# FPGA.net
KiCad netlist of a schematic drawn in Altium Designer
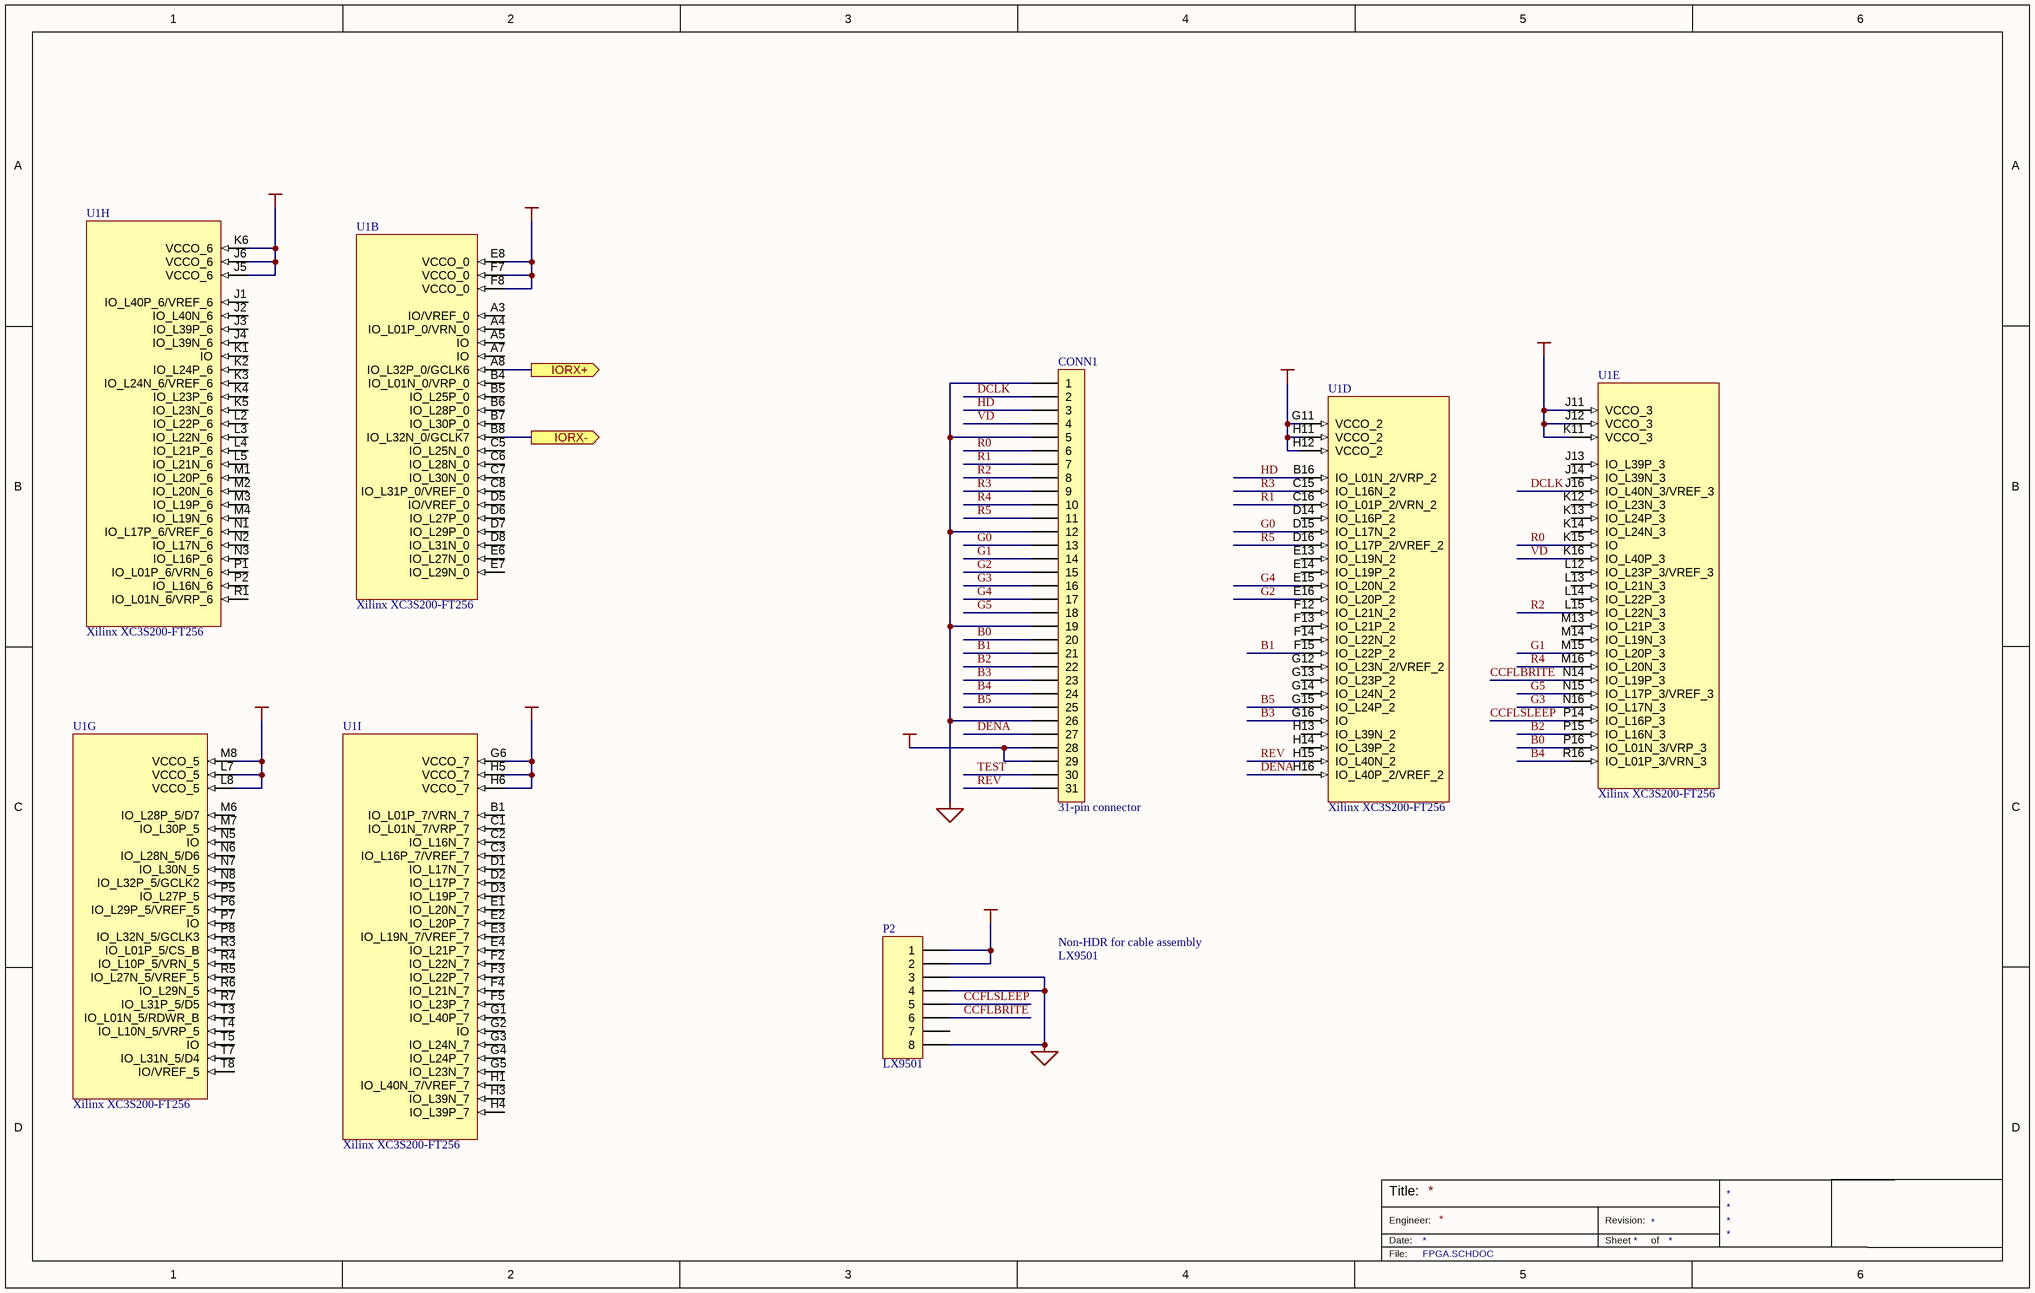
[diagram p0: FPGA.SCHDOC]

(export (version "E")
  (design (tool "Eeschema 10.0.6"))
  (components
    (comp (ref "CONN1")
      (value "31-pin connector")
      (footprint "DF9A-31S-1V")
      (libsource (lib "*") (part "CON31"))
    )
    (comp (ref "P2")
      (value "LX9501")
      (footprint "HDR1X8")
      (description "Header, 8-Pin")
      (fields (field (name "PUBLISHER") "Altium Limited"))
      (libsource (lib "Miscellaneous Connectors") (part "Header 8"))
    )
    (comp (ref "U1")
      (value "Xilinx XC3S200-FT256")
      (footprint "Xilinx FT256 BGA")
      (description "Xilinx Spartan-3 FPGA")
      (libsource (lib "parts") (part "XC3S200-FT256"))
    )
  )
  (nets
    (net (code "1") (name "+2.5VCC") (class "Default")
      (node (ref "U1") (pin "E8") (pinfunction "VCCO_0_E8") (pintype "input"))
      (node (ref "U1") (pin "F7") (pinfunction "VCCO_0_F7") (pintype "input"))
      (node (ref "U1") (pin "F8") (pinfunction "VCCO_0_F8") (pintype "input"))
    )
    (net (code "2") (name "+12VCC") (class "Default")
      (node (ref "P2") (pin "1") (pinfunction "1_1") (pintype "passive"))
      (node (ref "P2") (pin "2") (pinfunction "2_2") (pintype "passive"))
    )
    (net (code "3") (name "/B0") (class "Default")
      (node (ref "CONN1") (pin "20") (pinfunction "20_20") (pintype "passive"))
      (node (ref "U1") (pin "P16") (pinfunction "IO_L01N_3/VRP_3_P16") (pintype "input"))
    )
    (net (code "4") (name "/B1") (class "Default")
      (node (ref "CONN1") (pin "21") (pinfunction "21_21") (pintype "passive"))
      (node (ref "U1") (pin "F15") (pinfunction "IO_L22P_2_F15") (pintype "input"))
    )
    (net (code "5") (name "/B2") (class "Default")
      (node (ref "CONN1") (pin "22") (pinfunction "22_22") (pintype "passive"))
      (node (ref "U1") (pin "P15") (pinfunction "IO_L16N_3_P15") (pintype "input"))
    )
    (net (code "6") (name "/B3") (class "Default")
      (node (ref "CONN1") (pin "23") (pinfunction "23_23") (pintype "passive"))
      (node (ref "U1") (pin "G16") (pinfunction "IO_G16") (pintype "input"))
    )
    (net (code "7") (name "/B4") (class "Default")
      (node (ref "CONN1") (pin "24") (pinfunction "24_24") (pintype "passive"))
      (node (ref "U1") (pin "R16") (pinfunction "IO_L01P_3/VRN_3_R16") (pintype "input"))
    )
    (net (code "8") (name "/B5") (class "Default")
      (node (ref "CONN1") (pin "25") (pinfunction "25_25") (pintype "passive"))
      (node (ref "U1") (pin "G15") (pinfunction "IO_L24P_2_G15") (pintype "input"))
    )
    (net (code "9") (name "/CCFLBRITE") (class "Default")
      (node (ref "P2") (pin "6") (pinfunction "6_6") (pintype "passive"))
      (node (ref "U1") (pin "N14") (pinfunction "IO_L19P_3_N14") (pintype "input"))
    )
    (net (code "10") (name "/CCFLSLEEP") (class "Default")
      (node (ref "P2") (pin "5") (pinfunction "5_5") (pintype "passive"))
      (node (ref "U1") (pin "P14") (pinfunction "IO_L16P_3_P14") (pintype "input"))
    )
    (net (code "11") (name "/DCLK") (class "Default")
      (node (ref "CONN1") (pin "2") (pinfunction "2_2") (pintype "passive"))
      (node (ref "U1") (pin "J16") (pinfunction "IO_L40N_3/VREF_3_J16") (pintype "input"))
    )
    (net (code "12") (name "/DENA") (class "Default")
      (node (ref "CONN1") (pin "27") (pinfunction "27_27") (pintype "passive"))
      (node (ref "U1") (pin "H16") (pinfunction "IO_L40P_2/VREF_2_H16") (pintype "input"))
    )
    (net (code "13") (name "/G0") (class "Default")
      (node (ref "CONN1") (pin "13") (pinfunction "13_13") (pintype "passive"))
      (node (ref "U1") (pin "D15") (pinfunction "IO_L17N_2_D15") (pintype "input"))
    )
    (net (code "14") (name "/G1") (class "Default")
      (node (ref "CONN1") (pin "14") (pinfunction "14_14") (pintype "passive"))
      (node (ref "U1") (pin "M15") (pinfunction "IO_L20P_3_M15") (pintype "input"))
    )
    (net (code "15") (name "/G2") (class "Default")
      (node (ref "CONN1") (pin "15") (pinfunction "15_15") (pintype "passive"))
      (node (ref "U1") (pin "E16") (pinfunction "IO_L20P_2_E16") (pintype "input"))
    )
    (net (code "16") (name "/G3") (class "Default")
      (node (ref "CONN1") (pin "16") (pinfunction "16_16") (pintype "passive"))
      (node (ref "U1") (pin "N16") (pinfunction "IO_L17N_3_N16") (pintype "input"))
    )
    (net (code "17") (name "/G4") (class "Default")
      (node (ref "CONN1") (pin "17") (pinfunction "17_17") (pintype "passive"))
      (node (ref "U1") (pin "E15") (pinfunction "IO_L20N_2_E15") (pintype "input"))
    )
    (net (code "18") (name "/G5") (class "Default")
      (node (ref "CONN1") (pin "18") (pinfunction "18_18") (pintype "passive"))
      (node (ref "U1") (pin "N15") (pinfunction "IO_L17P_3/VREF_3_N15") (pintype "input"))
    )
    (net (code "19") (name "/HD") (class "Default")
      (node (ref "CONN1") (pin "3") (pinfunction "3_3") (pintype "passive"))
      (node (ref "U1") (pin "B16") (pinfunction "IO_L01N_2/VRP_2_B16") (pintype "input"))
    )
    (net (code "20") (name "/IORX+") (class "Default")
      (node (ref "U1") (pin "A8") (pinfunction "IO_L32P_0/GCLK6_A8") (pintype "input"))
    )
    (net (code "21") (name "/IORX-") (class "Default")
      (node (ref "U1") (pin "B8") (pinfunction "IO_L32N_0/GCLK7_B8") (pintype "input"))
    )
    (net (code "22") (name "/R0") (class "Default")
      (node (ref "CONN1") (pin "6") (pinfunction "6_6") (pintype "passive"))
      (node (ref "U1") (pin "K15") (pinfunction "IO_K15") (pintype "input"))
    )
    (net (code "23") (name "/R1") (class "Default")
      (node (ref "CONN1") (pin "7") (pinfunction "7_7") (pintype "passive"))
      (node (ref "U1") (pin "C16") (pinfunction "IO_L01P_2/VRN_2_C16") (pintype "input"))
    )
    (net (code "24") (name "/R2") (class "Default")
      (node (ref "CONN1") (pin "8") (pinfunction "8_8") (pintype "passive"))
      (node (ref "U1") (pin "L15") (pinfunction "IO_L22N_3_L15") (pintype "input"))
    )
    (net (code "25") (name "/R3") (class "Default")
      (node (ref "CONN1") (pin "9") (pinfunction "9_9") (pintype "passive"))
      (node (ref "U1") (pin "C15") (pinfunction "IO_L16N_2_C15") (pintype "input"))
    )
    (net (code "26") (name "/R4") (class "Default")
      (node (ref "CONN1") (pin "10") (pinfunction "10_10") (pintype "passive"))
      (node (ref "U1") (pin "M16") (pinfunction "IO_L20N_3_M16") (pintype "input"))
    )
    (net (code "27") (name "/R5") (class "Default")
      (node (ref "CONN1") (pin "11") (pinfunction "11_11") (pintype "passive"))
      (node (ref "U1") (pin "D16") (pinfunction "IO_L17P_2/VREF_2_D16") (pintype "input"))
    )
    (net (code "28") (name "/REV") (class "Default")
      (node (ref "CONN1") (pin "31") (pinfunction "31_31") (pintype "passive"))
      (node (ref "U1") (pin "H15") (pinfunction "IO_L40N_2_H15") (pintype "input"))
    )
    (net (code "29") (name "/TEST") (class "Default")
      (node (ref "CONN1") (pin "30") (pinfunction "30_30") (pintype "passive"))
    )
    (net (code "30") (name "/VD") (class "Default")
      (node (ref "CONN1") (pin "4") (pinfunction "4_4") (pintype "passive"))
      (node (ref "U1") (pin "K16") (pinfunction "IO_L40P_3_K16") (pintype "input"))
    )
    (net (code "31") (name "GND") (class "Default")
      (node (ref "CONN1") (pin "1") (pinfunction "1_1") (pintype "passive"))
      (node (ref "CONN1") (pin "12") (pinfunction "12_12") (pintype "passive"))
      (node (ref "CONN1") (pin "19") (pinfunction "19_19") (pintype "passive"))
      (node (ref "CONN1") (pin "26") (pinfunction "26_26") (pintype "passive"))
      (node (ref "CONN1") (pin "5") (pinfunction "5_5") (pintype "passive"))
      (node (ref "P2") (pin "3") (pinfunction "3_3") (pintype "passive"))
      (node (ref "P2") (pin "4") (pinfunction "4_4") (pintype "passive"))
      (node (ref "P2") (pin "8") (pinfunction "8_8") (pintype "passive"))
    )
    (net (code "32") (name "VCC") (class "Default")
      (node (ref "CONN1") (pin "28") (pinfunction "28_28") (pintype "passive"))
      (node (ref "CONN1") (pin "29") (pinfunction "29_29") (pintype "passive"))
      (node (ref "U1") (pin "G11") (pinfunction "VCCO_2_G11") (pintype "input"))
      (node (ref "U1") (pin "G6") (pinfunction "VCCO_7_G6") (pintype "input"))
      (node (ref "U1") (pin "H11") (pinfunction "VCCO_2_H11") (pintype "input"))
      (node (ref "U1") (pin "H12") (pinfunction "VCCO_2_H12") (pintype "input"))
      (node (ref "U1") (pin "H5") (pinfunction "VCCO_7_H5") (pintype "input"))
      (node (ref "U1") (pin "H6") (pinfunction "VCCO_7_H6") (pintype "input"))
      (node (ref "U1") (pin "J11") (pinfunction "VCCO_3_J11") (pintype "input"))
      (node (ref "U1") (pin "J12") (pinfunction "VCCO_3_J12") (pintype "input"))
      (node (ref "U1") (pin "J5") (pinfunction "VCCO_6_J5") (pintype "input"))
      (node (ref "U1") (pin "J6") (pinfunction "VCCO_6_J6") (pintype "input"))
      (node (ref "U1") (pin "K11") (pinfunction "VCCO_3_K11") (pintype "input"))
      (node (ref "U1") (pin "K6") (pinfunction "VCCO_6_K6") (pintype "input"))
      (node (ref "U1") (pin "L7") (pinfunction "VCCO_5_L7") (pintype "input"))
      (node (ref "U1") (pin "L8") (pinfunction "VCCO_5_L8") (pintype "input"))
      (node (ref "U1") (pin "M8") (pinfunction "VCCO_5_M8") (pintype "input"))
    )
    (net (code "33") (name "unconnected-(P2-Pad7)") (class "Default")
      (node (ref "P2") (pin "7") (pinfunction "7_7") (pintype "passive"))
    )
    (net (code "34") (name "unconnected-(U1B-IO-PadA5)") (class "Default")
      (node (ref "U1") (pin "A5") (pinfunction "IO_A5") (pintype "input"))
    )
    (net (code "35") (name "unconnected-(U1B-IO-PadA7)") (class "Default")
      (node (ref "U1") (pin "A7") (pinfunction "IO_A7") (pintype "input"))
    )
    (net (code "36") (name "unconnected-(U1B-IO_L01N_0{slash}VRP_0-PadB4)") (class "Default")
      (node (ref "U1") (pin "B4") (pinfunction "IO_L01N_0/VRP_0_B4") (pintype "input"))
    )
    (net (code "37") (name "unconnected-(U1B-IO_L01P_0{slash}VRN_0-PadA4)") (class "Default")
      (node (ref "U1") (pin "A4") (pinfunction "IO_L01P_0/VRN_0_A4") (pintype "input"))
    )
    (net (code "38") (name "unconnected-(U1B-IO_L25N_0-PadC5)") (class "Default")
      (node (ref "U1") (pin "C5") (pinfunction "IO_L25N_0_C5") (pintype "input"))
    )
    (net (code "39") (name "unconnected-(U1B-IO_L25P_0-PadB5)") (class "Default")
      (node (ref "U1") (pin "B5") (pinfunction "IO_L25P_0_B5") (pintype "input"))
    )
    (net (code "40") (name "unconnected-(U1B-IO_L27N_0-PadE6)") (class "Default")
      (node (ref "U1") (pin "E6") (pinfunction "IO_L27N_0_E6") (pintype "input"))
    )
    (net (code "41") (name "unconnected-(U1B-IO_L27P_0-PadD6)") (class "Default")
      (node (ref "U1") (pin "D6") (pinfunction "IO_L27P_0_D6") (pintype "input"))
    )
    (net (code "42") (name "unconnected-(U1B-IO_L28N_0-PadC6)") (class "Default")
      (node (ref "U1") (pin "C6") (pinfunction "IO_L28N_0_C6") (pintype "input"))
    )
    (net (code "43") (name "unconnected-(U1B-IO_L28P_0-PadB6)") (class "Default")
      (node (ref "U1") (pin "B6") (pinfunction "IO_L28P_0_B6") (pintype "input"))
    )
    (net (code "44") (name "unconnected-(U1B-IO_L29N_0-PadE7)") (class "Default")
      (node (ref "U1") (pin "E7") (pinfunction "IO_L29N_0_E7") (pintype "input"))
    )
    (net (code "45") (name "unconnected-(U1B-IO_L29P_0-PadD7)") (class "Default")
      (node (ref "U1") (pin "D7") (pinfunction "IO_L29P_0_D7") (pintype "input"))
    )
    (net (code "46") (name "unconnected-(U1B-IO_L30N_0-PadC7)") (class "Default")
      (node (ref "U1") (pin "C7") (pinfunction "IO_L30N_0_C7") (pintype "input"))
    )
    (net (code "47") (name "unconnected-(U1B-IO_L30P_0-PadB7)") (class "Default")
      (node (ref "U1") (pin "B7") (pinfunction "IO_L30P_0_B7") (pintype "input"))
    )
    (net (code "48") (name "unconnected-(U1B-IO_L31N_0-PadD8)") (class "Default")
      (node (ref "U1") (pin "D8") (pinfunction "IO_L31N_0_D8") (pintype "input"))
    )
    (net (code "49") (name "unconnected-(U1B-IO_L31P_0{slash}VREF_0-PadC8)") (class "Default")
      (node (ref "U1") (pin "C8") (pinfunction "IO_L31P_0/VREF_0_C8") (pintype "input"))
    )
    (net (code "50") (name "unconnected-(U1B-IO{slash}VREF_0-PadA3)") (class "Default")
      (node (ref "U1") (pin "A3") (pinfunction "IO/VREF_0_A3") (pintype "input"))
    )
    (net (code "51") (name "unconnected-(U1B-IO{slash}VREF_0-PadD5)") (class "Default")
      (node (ref "U1") (pin "D5") (pinfunction "IO/VREF_0_D5") (pintype "input"))
    )
    (net (code "52") (name "unconnected-(U1D-IO_L16P_2-PadD14)") (class "Default")
      (node (ref "U1") (pin "D14") (pinfunction "IO_L16P_2_D14") (pintype "input"))
    )
    (net (code "53") (name "unconnected-(U1D-IO_L19N_2-PadE13)") (class "Default")
      (node (ref "U1") (pin "E13") (pinfunction "IO_L19N_2_E13") (pintype "input"))
    )
    (net (code "54") (name "unconnected-(U1D-IO_L19P_2-PadE14)") (class "Default")
      (node (ref "U1") (pin "E14") (pinfunction "IO_L19P_2_E14") (pintype "input"))
    )
    (net (code "55") (name "unconnected-(U1D-IO_L21N_2-PadF12)") (class "Default")
      (node (ref "U1") (pin "F12") (pinfunction "IO_L21N_2_F12") (pintype "input"))
    )
    (net (code "56") (name "unconnected-(U1D-IO_L21P_2-PadF13)") (class "Default")
      (node (ref "U1") (pin "F13") (pinfunction "IO_L21P_2_F13") (pintype "input"))
    )
    (net (code "57") (name "unconnected-(U1D-IO_L22N_2-PadF14)") (class "Default")
      (node (ref "U1") (pin "F14") (pinfunction "IO_L22N_2_F14") (pintype "input"))
    )
    (net (code "58") (name "unconnected-(U1D-IO_L23N_2{slash}VREF_2-PadG12)") (class "Default")
      (node (ref "U1") (pin "G12") (pinfunction "IO_L23N_2/VREF_2_G12") (pintype "input"))
    )
    (net (code "59") (name "unconnected-(U1D-IO_L23P_2-PadG13)") (class "Default")
      (node (ref "U1") (pin "G13") (pinfunction "IO_L23P_2_G13") (pintype "input"))
    )
    (net (code "60") (name "unconnected-(U1D-IO_L24N_2-PadG14)") (class "Default")
      (node (ref "U1") (pin "G14") (pinfunction "IO_L24N_2_G14") (pintype "input"))
    )
    (net (code "61") (name "unconnected-(U1D-IO_L39N_2-PadH13)") (class "Default")
      (node (ref "U1") (pin "H13") (pinfunction "IO_L39N_2_H13") (pintype "input"))
    )
    (net (code "62") (name "unconnected-(U1D-IO_L39P_2-PadH14)") (class "Default")
      (node (ref "U1") (pin "H14") (pinfunction "IO_L39P_2_H14") (pintype "input"))
    )
    (net (code "63") (name "unconnected-(U1E-IO_L19N_3-PadM14)") (class "Default")
      (node (ref "U1") (pin "M14") (pinfunction "IO_L19N_3_M14") (pintype "input"))
    )
    (net (code "64") (name "unconnected-(U1E-IO_L21N_3-PadL13)") (class "Default")
      (node (ref "U1") (pin "L13") (pinfunction "IO_L21N_3_L13") (pintype "input"))
    )
    (net (code "65") (name "unconnected-(U1E-IO_L21P_3-PadM13)") (class "Default")
      (node (ref "U1") (pin "M13") (pinfunction "IO_L21P_3_M13") (pintype "input"))
    )
    (net (code "66") (name "unconnected-(U1E-IO_L22P_3-PadL14)") (class "Default")
      (node (ref "U1") (pin "L14") (pinfunction "IO_L22P_3_L14") (pintype "input"))
    )
    (net (code "67") (name "unconnected-(U1E-IO_L23N_3-PadK12)") (class "Default")
      (node (ref "U1") (pin "K12") (pinfunction "IO_L23N_3_K12") (pintype "input"))
    )
    (net (code "68") (name "unconnected-(U1E-IO_L23P_3{slash}VREF_3-PadL12)") (class "Default")
      (node (ref "U1") (pin "L12") (pinfunction "IO_L23P_3/VREF_3_L12") (pintype "input"))
    )
    (net (code "69") (name "unconnected-(U1E-IO_L24N_3-PadK14)") (class "Default")
      (node (ref "U1") (pin "K14") (pinfunction "IO_L24N_3_K14") (pintype "input"))
    )
    (net (code "70") (name "unconnected-(U1E-IO_L24P_3-PadK13)") (class "Default")
      (node (ref "U1") (pin "K13") (pinfunction "IO_L24P_3_K13") (pintype "input"))
    )
    (net (code "71") (name "unconnected-(U1E-IO_L39N_3-PadJ14)") (class "Default")
      (node (ref "U1") (pin "J14") (pinfunction "IO_L39N_3_J14") (pintype "input"))
    )
    (net (code "72") (name "unconnected-(U1E-IO_L39P_3-PadJ13)") (class "Default")
      (node (ref "U1") (pin "J13") (pinfunction "IO_L39P_3_J13") (pintype "input"))
    )
    (net (code "73") (name "unconnected-(U1G-IO-PadN5)") (class "Default")
      (node (ref "U1") (pin "N5") (pinfunction "IO_N5") (pintype "input"))
    )
    (net (code "74") (name "unconnected-(U1G-IO-PadP7)") (class "Default")
      (node (ref "U1") (pin "P7") (pinfunction "IO_P7") (pintype "input"))
    )
    (net (code "75") (name "unconnected-(U1G-IO-PadT5)") (class "Default")
      (node (ref "U1") (pin "T5") (pinfunction "IO_T5") (pintype "input"))
    )
    (net (code "76") (name "unconnected-(U1G-IO_L01N_5{slash}RDWR_B-PadT3)") (class "Default")
      (node (ref "U1") (pin "T3") (pinfunction "IO_L01N_5/RDWR_B_T3") (pintype "input"))
    )
    (net (code "77") (name "unconnected-(U1G-IO_L01P_5{slash}CS_B-PadR3)") (class "Default")
      (node (ref "U1") (pin "R3") (pinfunction "IO_L01P_5/CS_B_R3") (pintype "input"))
    )
    (net (code "78") (name "unconnected-(U1G-IO_L10N_5{slash}VRP_5-PadT4)") (class "Default")
      (node (ref "U1") (pin "T4") (pinfunction "IO_L10N_5/VRP_5_T4") (pintype "input"))
    )
    (net (code "79") (name "unconnected-(U1G-IO_L10P_5{slash}VRN_5-PadR4)") (class "Default")
      (node (ref "U1") (pin "R4") (pinfunction "IO_L10P_5/VRN_5_R4") (pintype "input"))
    )
    (net (code "80") (name "unconnected-(U1G-IO_L27N_5{slash}VREF_5-PadR5)") (class "Default")
      (node (ref "U1") (pin "R5") (pinfunction "IO_L27N_5/VREF_5_R5") (pintype "input"))
    )
    (net (code "81") (name "unconnected-(U1G-IO_L27P_5-PadP5)") (class "Default")
      (node (ref "U1") (pin "P5") (pinfunction "IO_L27P_5_P5") (pintype "input"))
    )
    (net (code "82") (name "unconnected-(U1G-IO_L28N_5{slash}D6-PadN6)") (class "Default")
      (node (ref "U1") (pin "N6") (pinfunction "IO_L28N_5/D6_N6") (pintype "input"))
    )
    (net (code "83") (name "unconnected-(U1G-IO_L28P_5{slash}D7-PadM6)") (class "Default")
      (node (ref "U1") (pin "M6") (pinfunction "IO_L28P_5/D7_M6") (pintype "input"))
    )
    (net (code "84") (name "unconnected-(U1G-IO_L29N_5-PadR6)") (class "Default")
      (node (ref "U1") (pin "R6") (pinfunction "IO_L29N_5_R6") (pintype "input"))
    )
    (net (code "85") (name "unconnected-(U1G-IO_L29P_5{slash}VREF_5-PadP6)") (class "Default")
      (node (ref "U1") (pin "P6") (pinfunction "IO_L29P_5/VREF_5_P6") (pintype "input"))
    )
    (net (code "86") (name "unconnected-(U1G-IO_L30N_5-PadN7)") (class "Default")
      (node (ref "U1") (pin "N7") (pinfunction "IO_L30N_5_N7") (pintype "input"))
    )
    (net (code "87") (name "unconnected-(U1G-IO_L30P_5-PadM7)") (class "Default")
      (node (ref "U1") (pin "M7") (pinfunction "IO_L30P_5_M7") (pintype "input"))
    )
    (net (code "88") (name "unconnected-(U1G-IO_L31N_5{slash}D4-PadT7)") (class "Default")
      (node (ref "U1") (pin "T7") (pinfunction "IO_L31N_5/D4_T7") (pintype "input"))
    )
    (net (code "89") (name "unconnected-(U1G-IO_L31P_5{slash}D5-PadR7)") (class "Default")
      (node (ref "U1") (pin "R7") (pinfunction "IO_L31P_5/D5_R7") (pintype "input"))
    )
    (net (code "90") (name "unconnected-(U1G-IO_L32N_5{slash}GCLK3-PadP8)") (class "Default")
      (node (ref "U1") (pin "P8") (pinfunction "IO_L32N_5/GCLK3_P8") (pintype "input"))
    )
    (net (code "91") (name "unconnected-(U1G-IO_L32P_5{slash}GCLK2-PadN8)") (class "Default")
      (node (ref "U1") (pin "N8") (pinfunction "IO_L32P_5/GCLK2_N8") (pintype "input"))
    )
    (net (code "92") (name "unconnected-(U1G-IO{slash}VREF_5-PadT8)") (class "Default")
      (node (ref "U1") (pin "T8") (pinfunction "IO/VREF_5_T8") (pintype "input"))
    )
    (net (code "93") (name "unconnected-(U1H-IO-PadK1)") (class "Default")
      (node (ref "U1") (pin "K1") (pinfunction "IO_K1") (pintype "input"))
    )
    (net (code "94") (name "unconnected-(U1H-IO_L01N_6{slash}VRP_6-PadR1)") (class "Default")
      (node (ref "U1") (pin "R1") (pinfunction "IO_L01N_6/VRP_6_R1") (pintype "input"))
    )
    (net (code "95") (name "unconnected-(U1H-IO_L01P_6{slash}VRN_6-PadP1)") (class "Default")
      (node (ref "U1") (pin "P1") (pinfunction "IO_L01P_6/VRN_6_P1") (pintype "input"))
    )
    (net (code "96") (name "unconnected-(U1H-IO_L16N_6-PadP2)") (class "Default")
      (node (ref "U1") (pin "P2") (pinfunction "IO_L16N_6_P2") (pintype "input"))
    )
    (net (code "97") (name "unconnected-(U1H-IO_L16P_6-PadN3)") (class "Default")
      (node (ref "U1") (pin "N3") (pinfunction "IO_L16P_6_N3") (pintype "input"))
    )
    (net (code "98") (name "unconnected-(U1H-IO_L17N_6-PadN2)") (class "Default")
      (node (ref "U1") (pin "N2") (pinfunction "IO_L17N_6_N2") (pintype "input"))
    )
    (net (code "99") (name "unconnected-(U1H-IO_L17P_6{slash}VREF_6-PadN1)") (class "Default")
      (node (ref "U1") (pin "N1") (pinfunction "IO_L17P_6/VREF_6_N1") (pintype "input"))
    )
    (net (code "100") (name "unconnected-(U1H-IO_L19N_6-PadM4)") (class "Default")
      (node (ref "U1") (pin "M4") (pinfunction "IO_L19N_6_M4") (pintype "input"))
    )
    (net (code "101") (name "unconnected-(U1H-IO_L19P_6-PadM3)") (class "Default")
      (node (ref "U1") (pin "M3") (pinfunction "IO_L19P_6_M3") (pintype "input"))
    )
    (net (code "102") (name "unconnected-(U1H-IO_L20N_6-PadM2)") (class "Default")
      (node (ref "U1") (pin "M2") (pinfunction "IO_L20N_6_M2") (pintype "input"))
    )
    (net (code "103") (name "unconnected-(U1H-IO_L20P_6-PadM1)") (class "Default")
      (node (ref "U1") (pin "M1") (pinfunction "IO_L20P_6_M1") (pintype "input"))
    )
    (net (code "104") (name "unconnected-(U1H-IO_L21N_6-PadL5)") (class "Default")
      (node (ref "U1") (pin "L5") (pinfunction "IO_L21N_6_L5") (pintype "input"))
    )
    (net (code "105") (name "unconnected-(U1H-IO_L21P_6-PadL4)") (class "Default")
      (node (ref "U1") (pin "L4") (pinfunction "IO_L21P_6_L4") (pintype "input"))
    )
    (net (code "106") (name "unconnected-(U1H-IO_L22N_6-PadL3)") (class "Default")
      (node (ref "U1") (pin "L3") (pinfunction "IO_L22N_6_L3") (pintype "input"))
    )
    (net (code "107") (name "unconnected-(U1H-IO_L22P_6-PadL2)") (class "Default")
      (node (ref "U1") (pin "L2") (pinfunction "IO_L22P_6_L2") (pintype "input"))
    )
    (net (code "108") (name "unconnected-(U1H-IO_L23N_6-PadK5)") (class "Default")
      (node (ref "U1") (pin "K5") (pinfunction "IO_L23N_6_K5") (pintype "input"))
    )
    (net (code "109") (name "unconnected-(U1H-IO_L23P_6-PadK4)") (class "Default")
      (node (ref "U1") (pin "K4") (pinfunction "IO_L23P_6_K4") (pintype "input"))
    )
    (net (code "110") (name "unconnected-(U1H-IO_L24N_6{slash}VREF_6-PadK3)") (class "Default")
      (node (ref "U1") (pin "K3") (pinfunction "IO_L24N_6/VREF_6_K3") (pintype "input"))
    )
    (net (code "111") (name "unconnected-(U1H-IO_L24P_6-PadK2)") (class "Default")
      (node (ref "U1") (pin "K2") (pinfunction "IO_L24P_6_K2") (pintype "input"))
    )
    (net (code "112") (name "unconnected-(U1H-IO_L39N_6-PadJ4)") (class "Default")
      (node (ref "U1") (pin "J4") (pinfunction "IO_L39N_6_J4") (pintype "input"))
    )
    (net (code "113") (name "unconnected-(U1H-IO_L39P_6-PadJ3)") (class "Default")
      (node (ref "U1") (pin "J3") (pinfunction "IO_L39P_6_J3") (pintype "input"))
    )
    (net (code "114") (name "unconnected-(U1H-IO_L40N_6-PadJ2)") (class "Default")
      (node (ref "U1") (pin "J2") (pinfunction "IO_L40N_6_J2") (pintype "input"))
    )
    (net (code "115") (name "unconnected-(U1H-IO_L40P_6{slash}VREF_6-PadJ1)") (class "Default")
      (node (ref "U1") (pin "J1") (pinfunction "IO_L40P_6/VREF_6_J1") (pintype "input"))
    )
    (net (code "116") (name "unconnected-(U1I-IO-PadG2)") (class "Default")
      (node (ref "U1") (pin "G2") (pinfunction "IO_G2") (pintype "input"))
    )
    (net (code "117") (name "unconnected-(U1I-IO_L01N_7{slash}VRP_7-PadC1)") (class "Default")
      (node (ref "U1") (pin "C1") (pinfunction "IO_L01N_7/VRP_7_C1") (pintype "input"))
    )
    (net (code "118") (name "unconnected-(U1I-IO_L01P_7{slash}VRN_7-PadB1)") (class "Default")
      (node (ref "U1") (pin "B1") (pinfunction "IO_L01P_7/VRN_7_B1") (pintype "input"))
    )
    (net (code "119") (name "unconnected-(U1I-IO_L16N_7-PadC2)") (class "Default")
      (node (ref "U1") (pin "C2") (pinfunction "IO_L16N_7_C2") (pintype "input"))
    )
    (net (code "120") (name "unconnected-(U1I-IO_L16P_7{slash}VREF_7-PadC3)") (class "Default")
      (node (ref "U1") (pin "C3") (pinfunction "IO_L16P_7/VREF_7_C3") (pintype "input"))
    )
    (net (code "121") (name "unconnected-(U1I-IO_L17N_7-PadD1)") (class "Default")
      (node (ref "U1") (pin "D1") (pinfunction "IO_L17N_7_D1") (pintype "input"))
    )
    (net (code "122") (name "unconnected-(U1I-IO_L17P_7-PadD2)") (class "Default")
      (node (ref "U1") (pin "D2") (pinfunction "IO_L17P_7_D2") (pintype "input"))
    )
    (net (code "123") (name "unconnected-(U1I-IO_L19N_7{slash}VREF_7-PadE3)") (class "Default")
      (node (ref "U1") (pin "E3") (pinfunction "IO_L19N_7/VREF_7_E3") (pintype "input"))
    )
    (net (code "124") (name "unconnected-(U1I-IO_L19P_7-PadD3)") (class "Default")
      (node (ref "U1") (pin "D3") (pinfunction "IO_L19P_7_D3") (pintype "input"))
    )
    (net (code "125") (name "unconnected-(U1I-IO_L20N_7-PadE1)") (class "Default")
      (node (ref "U1") (pin "E1") (pinfunction "IO_L20N_7_E1") (pintype "input"))
    )
    (net (code "126") (name "unconnected-(U1I-IO_L20P_7-PadE2)") (class "Default")
      (node (ref "U1") (pin "E2") (pinfunction "IO_L20P_7_E2") (pintype "input"))
    )
    (net (code "127") (name "unconnected-(U1I-IO_L21N_7-PadF4)") (class "Default")
      (node (ref "U1") (pin "F4") (pinfunction "IO_L21N_7_F4") (pintype "input"))
    )
    (net (code "128") (name "unconnected-(U1I-IO_L21P_7-PadE4)") (class "Default")
      (node (ref "U1") (pin "E4") (pinfunction "IO_L21P_7_E4") (pintype "input"))
    )
    (net (code "129") (name "unconnected-(U1I-IO_L22N_7-PadF2)") (class "Default")
      (node (ref "U1") (pin "F2") (pinfunction "IO_L22N_7_F2") (pintype "input"))
    )
    (net (code "130") (name "unconnected-(U1I-IO_L22P_7-PadF3)") (class "Default")
      (node (ref "U1") (pin "F3") (pinfunction "IO_L22P_7_F3") (pintype "input"))
    )
    (net (code "131") (name "unconnected-(U1I-IO_L23N_7-PadG5)") (class "Default")
      (node (ref "U1") (pin "G5") (pinfunction "IO_L23N_7_G5") (pintype "input"))
    )
    (net (code "132") (name "unconnected-(U1I-IO_L23P_7-PadF5)") (class "Default")
      (node (ref "U1") (pin "F5") (pinfunction "IO_L23P_7_F5") (pintype "input"))
    )
    (net (code "133") (name "unconnected-(U1I-IO_L24N_7-PadG3)") (class "Default")
      (node (ref "U1") (pin "G3") (pinfunction "IO_L24N_7_G3") (pintype "input"))
    )
    (net (code "134") (name "unconnected-(U1I-IO_L24P_7-PadG4)") (class "Default")
      (node (ref "U1") (pin "G4") (pinfunction "IO_L24P_7_G4") (pintype "input"))
    )
    (net (code "135") (name "unconnected-(U1I-IO_L39N_7-PadH3)") (class "Default")
      (node (ref "U1") (pin "H3") (pinfunction "IO_L39N_7_H3") (pintype "input"))
    )
    (net (code "136") (name "unconnected-(U1I-IO_L39P_7-PadH4)") (class "Default")
      (node (ref "U1") (pin "H4") (pinfunction "IO_L39P_7_H4") (pintype "input"))
    )
    (net (code "137") (name "unconnected-(U1I-IO_L40N_7{slash}VREF_7-PadH1)") (class "Default")
      (node (ref "U1") (pin "H1") (pinfunction "IO_L40N_7/VREF_7_H1") (pintype "input"))
    )
    (net (code "138") (name "unconnected-(U1I-IO_L40P_7-PadG1)") (class "Default")
      (node (ref "U1") (pin "G1") (pinfunction "IO_L40P_7_G1") (pintype "input"))
    )
  )
)
